# rf_router_trsw.net
KiCad netlist of a schematic drawn in Altium Designer
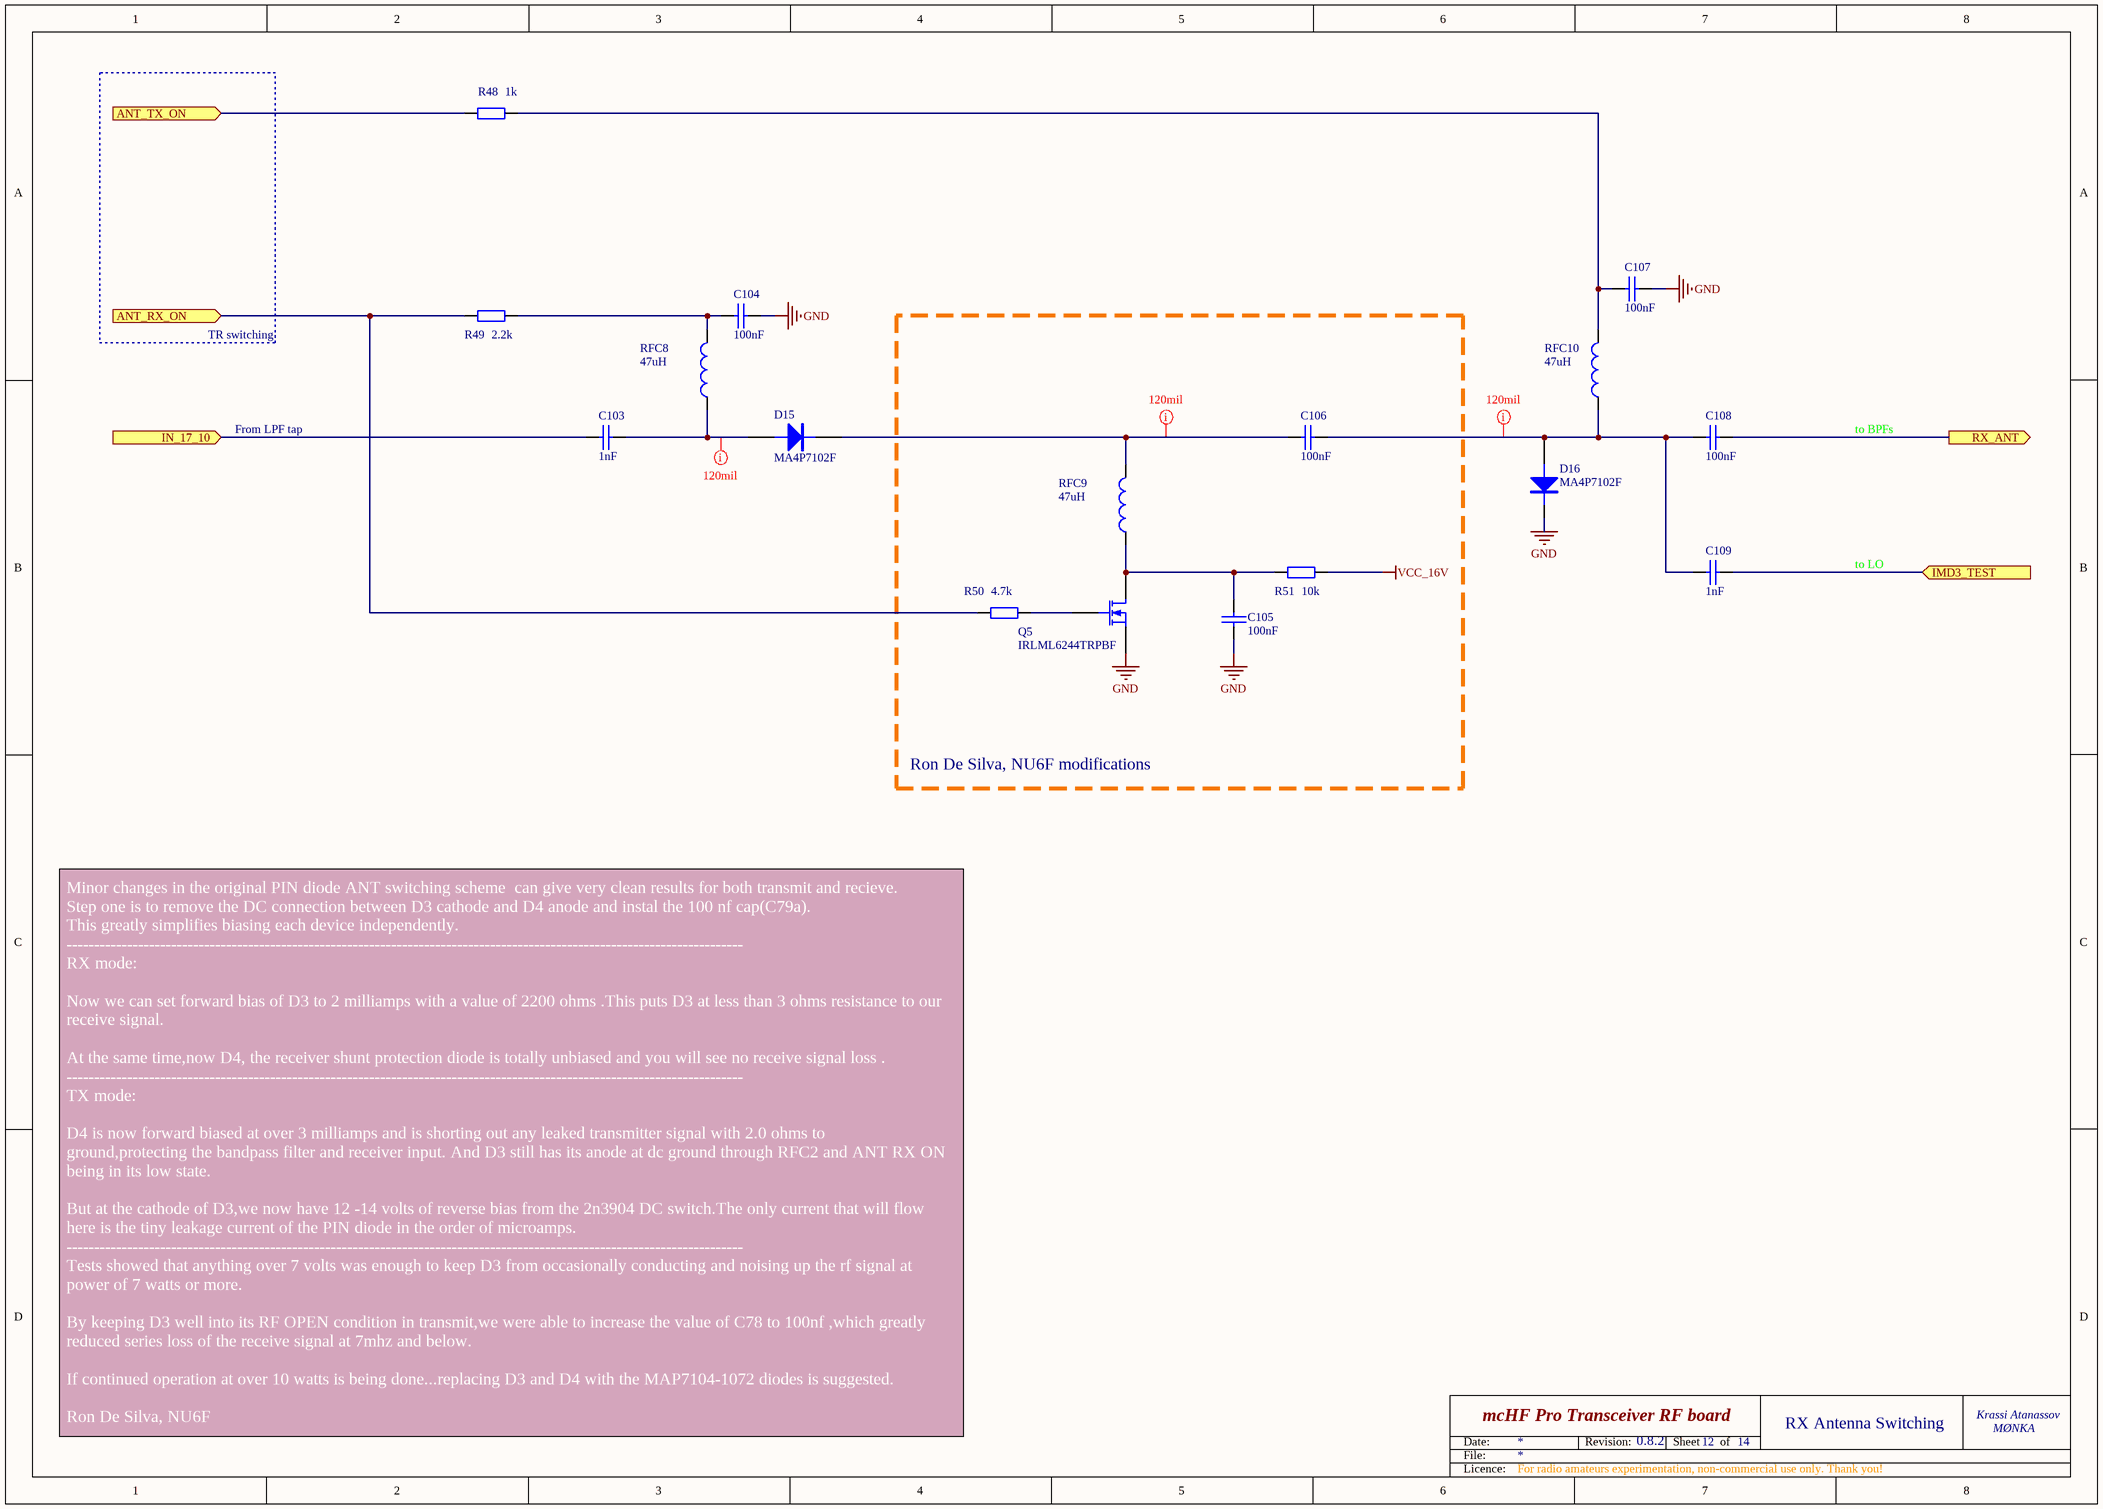
[diagram p0: rf_router_trsw.SchDoc]

(export (version "E")
  (design (tool "Eeschema 10.0.6"))
  (components
    (comp (ref "C103")
      (value "1nF")
      (footprint "0805")
      (description "Capacitor")
      (fields (field (name "VOLTAGE") "100V"))
      (libsource (lib "mcHF_rf") (part "CAP"))
    )
    (comp (ref "C104")
      (value "100nF")
      (footprint "0805")
      (description "Capacitor")
      (fields (field (name "VOLTAGE") "100V"))
      (libsource (lib "mcHF_rf") (part "CAP"))
    )
    (comp (ref "C105")
      (value "100nF")
      (footprint "0805")
      (description "Capacitor")
      (fields (field (name "VOLTAGE") "100V"))
      (libsource (lib "mcHF_rf") (part "CAP"))
    )
    (comp (ref "C106")
      (value "100nF")
      (footprint "0805")
      (description "Capacitor")
      (fields (field (name "VOLTAGE") "100V"))
      (libsource (lib "mcHF_rf") (part "CAP"))
    )
    (comp (ref "C107")
      (value "100nF")
      (footprint "0805")
      (description "Capacitor")
      (fields (field (name "VOLTAGE") "100V"))
      (libsource (lib "mcHF_rf") (part "CAP"))
    )
    (comp (ref "C108")
      (value "100nF")
      (footprint "0805")
      (description "Capacitor")
      (fields (field (name "VOLTAGE") "100V"))
      (libsource (lib "mcHF_rf") (part "CAP"))
    )
    (comp (ref "C109")
      (value "1nF")
      (footprint "0805")
      (description "Capacitor")
      (fields (field (name "VOLTAGE") "100V"))
      (libsource (lib "mcHF_rf") (part "CAP"))
    )
    (comp (ref "D15")
      (value "MA4P7102F")
      (footprint "1072T")
      (description "MELF & HIPAX PIN Diod")
      (libsource (lib "mcHF_rf") (part "MA4P7102F"))
    )
    (comp (ref "D16")
      (value "MA4P7102F")
      (footprint "1072T")
      (description "MELF & HIPAX PIN Diod")
      (libsource (lib "mcHF_rf") (part "MA4P7102F"))
    )
    (comp (ref "Q5")
      (value "IRLML6244TRPBF")
      (footprint "SOT-23-Pro")
      (description "N-Channel MOSFET")
      (libsource (lib "mcHF_ui_b") (part "MOSFET-N"))
    )
    (comp (ref "R48")
      (value "1k")
      (footprint "0805")
      (description "Resistor")
      (libsource (lib "") (part "RES_1"))
    )
    (comp (ref "R49")
      (value "2.2k")
      (footprint "0805")
      (description "Resistor")
      (libsource (lib "mcHF_rf") (part "RES"))
    )
    (comp (ref "R50")
      (value "4.7k")
      (footprint "0805")
      (description "Resistor")
      (libsource (lib "mcHF_rf") (part "RES"))
    )
    (comp (ref "R51")
      (value "10k")
      (footprint "0805")
      (description "Resistor")
      (libsource (lib "mcHF_rf") (part "RES"))
    )
    (comp (ref "RFC8")
      (value "47uH")
      (footprint "0805")
      (description "INDUCTOR, SIGNAL LINE, 47UH, 1005")
      (libsource (lib "mcHF_rf") (part "TDK-NLV25T"))
    )
    (comp (ref "RFC9")
      (value "47uH")
      (footprint "0805")
      (description "INDUCTOR, SIGNAL LINE, 47UH, 1005")
      (libsource (lib "mcHF_rf") (part "TDK-NLV25T"))
    )
    (comp (ref "RFC10")
      (value "47uH")
      (footprint "0805")
      (description "INDUCTOR, SIGNAL LINE, 47UH, 1005")
      (libsource (lib "mcHF_rf") (part "TDK-NLV25T"))
    )
  )
  (nets
    (net (code "1") (name "/ANT_RX_ON") (class "Default")
      (node (ref "R49") (pin "1") (pinfunction "1_1") (pintype "passive"))
      (node (ref "R50") (pin "1") (pinfunction "1_1") (pintype "passive"))
    )
    (net (code "2") (name "/ANT_TX_ON") (class "Default")
      (node (ref "R48") (pin "2") (pinfunction "2_2") (pintype "passive"))
    )
    (net (code "3") (name "/IMD3_TEST") (class "Default")
      (node (ref "C109") (pin "1") (pinfunction "1_1") (pintype "passive"))
    )
    (net (code "4") (name "/IN_17_10") (class "Default")
      (node (ref "C103") (pin "2") (pinfunction "2_2") (pintype "passive"))
    )
    (net (code "5") (name "/RX_ANT") (class "Default")
      (node (ref "C108") (pin "1") (pinfunction "1_1") (pintype "passive"))
    )
    (net (code "6") (name "GND") (class "Default")
      (node (ref "C104") (pin "1") (pinfunction "1_1") (pintype "passive"))
      (node (ref "C105") (pin "2") (pinfunction "2_2") (pintype "passive"))
      (node (ref "C107") (pin "1") (pinfunction "1_1") (pintype "passive"))
      (node (ref "D16") (pin "1") (pinfunction "K_1") (pintype "passive"))
      (node (ref "Q5") (pin "2") (pinfunction "S_2") (pintype "passive"))
    )
    (net (code "7") (name "Net-(C104-Pad2)") (class "Default")
      (node (ref "C104") (pin "2") (pinfunction "2_2") (pintype "passive"))
      (node (ref "R49") (pin "2") (pinfunction "2_2") (pintype "passive"))
      (node (ref "RFC8") (pin "2") (pinfunction "2_2") (pintype "passive"))
    )
    (net (code "8") (name "Net-(C107-Pad2)") (class "Default")
      (node (ref "C107") (pin "2") (pinfunction "2_2") (pintype "passive"))
      (node (ref "R48") (pin "1") (pinfunction "1_1") (pintype "passive"))
      (node (ref "RFC10") (pin "2") (pinfunction "2_2") (pintype "passive"))
    )
    (net (code "9") (name "Net-(D15-A)") (class "Default")
      (node (ref "C103") (pin "1") (pinfunction "1_1") (pintype "passive"))
      (node (ref "D15") (pin "2") (pinfunction "A_2") (pintype "passive"))
      (node (ref "RFC8") (pin "1") (pinfunction "1_1") (pintype "passive"))
    )
    (net (code "10") (name "Net-(D15-K)") (class "Default")
      (node (ref "C106") (pin "2") (pinfunction "2_2") (pintype "passive"))
      (node (ref "D15") (pin "1") (pinfunction "K_1") (pintype "passive"))
      (node (ref "RFC9") (pin "2") (pinfunction "2_2") (pintype "passive"))
    )
    (net (code "11") (name "Net-(D16-A)") (class "Default")
      (node (ref "C106") (pin "1") (pinfunction "1_1") (pintype "passive"))
      (node (ref "C108") (pin "2") (pinfunction "2_2") (pintype "passive"))
      (node (ref "C109") (pin "2") (pinfunction "2_2") (pintype "passive"))
      (node (ref "D16") (pin "2") (pinfunction "A_2") (pintype "passive"))
      (node (ref "RFC10") (pin "1") (pinfunction "1_1") (pintype "passive"))
    )
    (net (code "12") (name "Net-(Q5-D)") (class "Default")
      (node (ref "C105") (pin "1") (pinfunction "1_1") (pintype "passive"))
      (node (ref "Q5") (pin "3") (pinfunction "D_3") (pintype "passive"))
      (node (ref "R51") (pin "1") (pinfunction "1_1") (pintype "passive"))
      (node (ref "RFC9") (pin "1") (pinfunction "1_1") (pintype "passive"))
    )
    (net (code "13") (name "Net-(Q5-G)") (class "Default")
      (node (ref "Q5") (pin "1") (pinfunction "G_1") (pintype "passive"))
      (node (ref "R50") (pin "2") (pinfunction "2_2") (pintype "passive"))
    )
    (net (code "14") (name "VCC_16V") (class "Default")
      (node (ref "R51") (pin "2") (pinfunction "2_2") (pintype "passive"))
    )
  )
)
